# Sheet1.net
KiCad netlist of a schematic drawn in Altium Designer
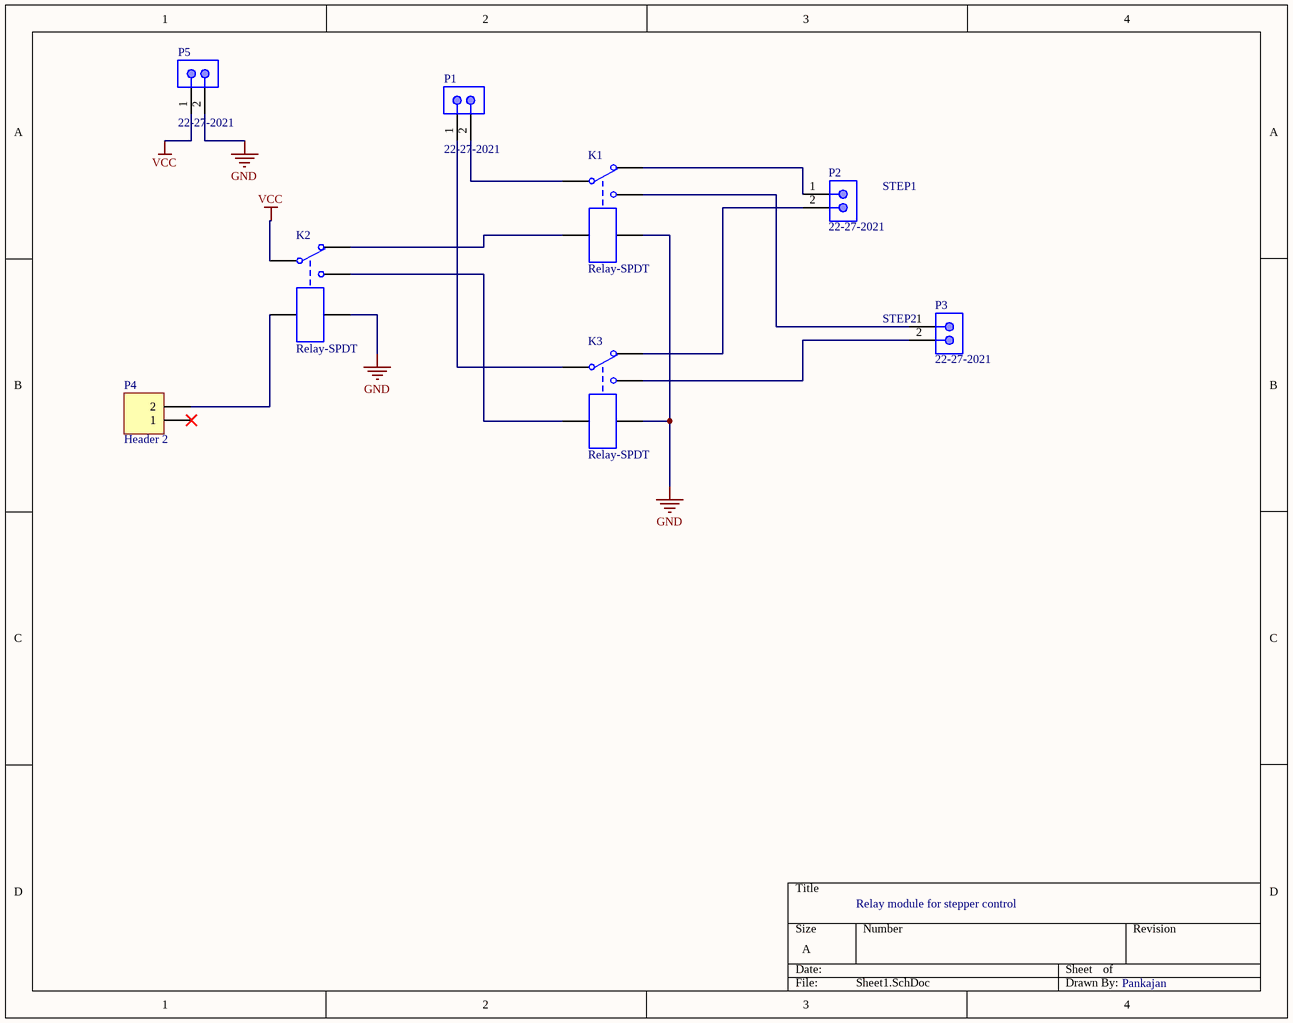
[diagram p0: Sheet1.SchDoc]

(export (version "E")
  (design (tool "Eeschema 10.0.6"))
  (components
    (comp (ref "K1")
      (value "Relay-SPDT")
      (footprint "MODULE5B")
      (description "Single-Pole Dual-Throw Relay")
      (fields (field (name "PUBLISHER") "Altium Limited"))
      (libsource (lib "Miscellaneous Devices") (part "Relay-SPDT"))
    )
    (comp (ref "K2")
      (value "Relay-SPDT")
      (footprint "MODULE5B")
      (description "Single-Pole Dual-Throw Relay")
      (fields (field (name "PUBLISHER") "Altium Limited"))
      (libsource (lib "Miscellaneous Devices") (part "Relay-SPDT"))
    )
    (comp (ref "K3")
      (value "Relay-SPDT")
      (footprint "MODULE5B")
      (description "Single-Pole Dual-Throw Relay")
      (fields (field (name "PUBLISHER") "Altium Limited"))
      (libsource (lib "Miscellaneous Devices") (part "Relay-SPDT"))
    )
    (comp (ref "P1")
      (value "22-27-2021")
      (footprint "MOLX-22-27-2021_V")
      (fields (field (name "MANUFACTURER") "Molex") (field (name "PARTNUMBER") "0022272021"))
      (libsource (lib "Altium Content Vault") (part "CN-1P-M-R2"))
    )
    (comp (ref "P2")
      (value "22-27-2021")
      (footprint "MOLX-22-27-2021_V")
      (fields (field (name "MANUFACTURER") "Molex") (field (name "PARTNUMBER") "0022272021"))
      (libsource (lib "") (part "CN-1P-M-R2_1"))
    )
    (comp (ref "P3")
      (value "22-27-2021")
      (footprint "MOLX-22-27-2021_V")
      (fields (field (name "MANUFACTURER") "Molex") (field (name "PARTNUMBER") "0022272021"))
      (libsource (lib "") (part "CN-1P-M-R2_1"))
    )
    (comp (ref "P4")
      (value "Header 2")
      (footprint "HDR1X2")
      (description "Header, 2-Pin")
      (fields (field (name "PUBLISHER") "Altium Limited"))
      (libsource (lib "Miscellaneous Connectors") (part "Header 2"))
    )
    (comp (ref "P5")
      (value "22-27-2021")
      (footprint "MOLX-22-27-2021_V")
      (fields (field (name "MANUFACTURER") "Molex") (field (name "PARTNUMBER") "0022272021"))
      (libsource (lib "Altium Content Vault") (part "CN-1P-M-R2"))
    )
  )
  (nets
    (net (code "1") (name "GND") (class "Default")
      (node (ref "K1") (pin "5") (pinfunction "5_5") (pintype "passive"))
      (node (ref "K2") (pin "5") (pinfunction "5_5") (pintype "passive"))
      (node (ref "K3") (pin "5") (pinfunction "5_5") (pintype "passive"))
      (node (ref "P5") (pin "2") (pinfunction "2_2") (pintype "passive"))
    )
    (net (code "2") (name "Net-(K1-Pad1)") (class "Default")
      (node (ref "K1") (pin "1") (pinfunction "1_1") (pintype "passive"))
      (node (ref "P1") (pin "2") (pinfunction "2_2") (pintype "passive"))
    )
    (net (code "3") (name "Net-(K1-Pad2)") (class "Default")
      (node (ref "K1") (pin "2") (pinfunction "2_2") (pintype "passive"))
      (node (ref "P2") (pin "1") (pinfunction "1_1") (pintype "passive"))
    )
    (net (code "4") (name "Net-(K1-Pad3)") (class "Default")
      (node (ref "K1") (pin "3") (pinfunction "3_3") (pintype "passive"))
      (node (ref "P3") (pin "1") (pinfunction "1_1") (pintype "passive"))
    )
    (net (code "5") (name "Net-(K1-Pad4)") (class "Default")
      (node (ref "K1") (pin "4") (pinfunction "4_4") (pintype "passive"))
      (node (ref "K2") (pin "2") (pinfunction "2_2") (pintype "passive"))
    )
    (net (code "6") (name "Net-(K2-Pad3)") (class "Default")
      (node (ref "K2") (pin "3") (pinfunction "3_3") (pintype "passive"))
      (node (ref "K3") (pin "4") (pinfunction "4_4") (pintype "passive"))
    )
    (net (code "7") (name "Net-(K2-Pad4)") (class "Default")
      (node (ref "K2") (pin "4") (pinfunction "4_4") (pintype "passive"))
      (node (ref "P4") (pin "2") (pinfunction "2_2") (pintype "passive"))
    )
    (net (code "8") (name "Net-(K3-Pad1)") (class "Default")
      (node (ref "K3") (pin "1") (pinfunction "1_1") (pintype "passive"))
      (node (ref "P1") (pin "1") (pinfunction "1_1") (pintype "passive"))
    )
    (net (code "9") (name "Net-(K3-Pad2)") (class "Default")
      (node (ref "K3") (pin "2") (pinfunction "2_2") (pintype "passive"))
      (node (ref "P2") (pin "2") (pinfunction "2_2") (pintype "passive"))
    )
    (net (code "10") (name "Net-(K3-Pad3)") (class "Default")
      (node (ref "K3") (pin "3") (pinfunction "3_3") (pintype "passive"))
      (node (ref "P3") (pin "2") (pinfunction "2_2") (pintype "passive"))
    )
    (net (code "11") (name "VCC") (class "Default")
      (node (ref "K2") (pin "1") (pinfunction "1_1") (pintype "passive"))
      (node (ref "P5") (pin "1") (pinfunction "1_1") (pintype "passive"))
    )
    (net (code "12") (name "unconnected-(P4-Pad1)") (class "Default")
      (node (ref "P4") (pin "1") (pinfunction "1_1") (pintype "passive+no_connect"))
    )
  )
)
